# sensorboard1.net
KiCad netlist of a schematic drawn in EAGLE
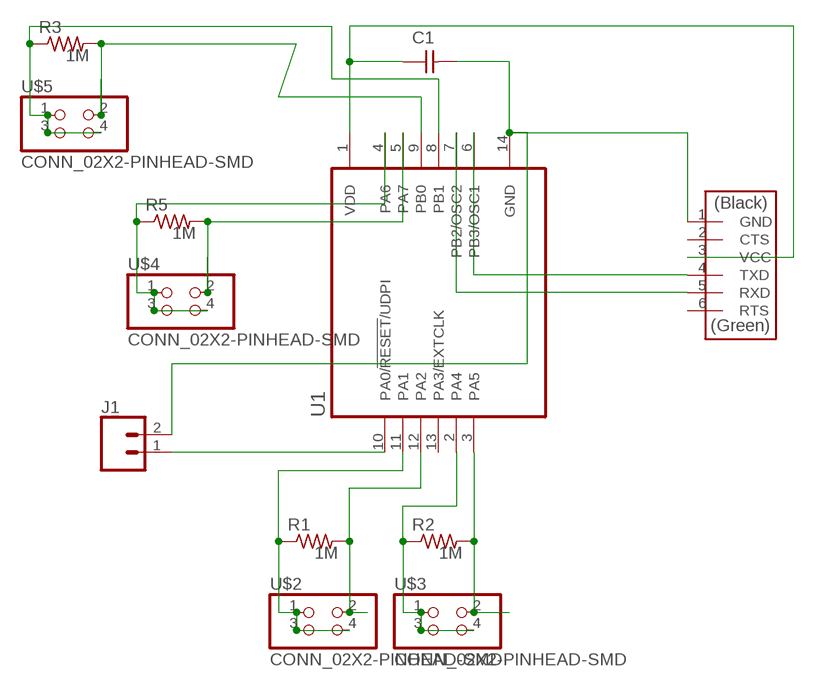
[diagram p0: schematic, sheet 1]

(export (version "E")
  (design (tool "Eeschema 10.0.6"))
  (components
    (comp (ref "C1")
      (value "CAP_UNPOLARIZEDFAB")
      (footprint "eagle-import:C1206FAB")
      (libsource (lib "eagle-import") (part "CAP_UNPOLARIZEDFAB"))
    )
    (comp (ref "J1")
      (value "CONN_02LOCK_LONGPADS")
      (footprint "eagle-import:1X02_LOCK_LONGPADS")
      (libsource (lib "eagle-import") (part "CONN_02LOCK_LONGPADS"))
    )
    (comp (ref "R1")
      (value "R1206FAB")
      (footprint "eagle-import:R1206FAB")
      (fields (field (name "R1") "1M"))
      (libsource (lib "eagle-import") (part "R1206FAB"))
    )
    (comp (ref "R2")
      (value "R1206FAB")
      (footprint "eagle-import:R1206FAB")
      (fields (field (name "R1") "1M"))
      (libsource (lib "eagle-import") (part "R1206FAB"))
    )
    (comp (ref "R3")
      (value "R1206FAB")
      (footprint "eagle-import:R1206FAB")
      (fields (field (name "R1") "1M"))
      (libsource (lib "eagle-import") (part "R1206FAB"))
    )
    (comp (ref "R5")
      (value "R1206FAB")
      (footprint "eagle-import:R1206FAB")
      (fields (field (name "R1") "1M"))
      (libsource (lib "eagle-import") (part "R1206FAB"))
    )
    (comp (ref "U$1")
      (value "CONN_06_FTDI-SMD-HEADER")
      (footprint "eagle-import:1X06SMD")
      (libsource (lib "eagle-import") (part "CONN_06_FTDI-SMD-HEADER"))
    )
    (comp (ref "U$2")
      (value "CONN_02X2-PINHEAD-SMD")
      (footprint "eagle-import:2X02SMD")
      (libsource (lib "eagle-import") (part "CONN_02X2-PINHEAD-SMD"))
    )
    (comp (ref "U$3")
      (value "CONN_02X2-PINHEAD-SMD")
      (footprint "eagle-import:2X02SMD")
      (libsource (lib "eagle-import") (part "CONN_02X2-PINHEAD-SMD"))
    )
    (comp (ref "U$4")
      (value "CONN_02X2-PINHEAD-SMD")
      (footprint "eagle-import:2X02SMD")
      (libsource (lib "eagle-import") (part "CONN_02X2-PINHEAD-SMD"))
    )
    (comp (ref "U$5")
      (value "CONN_02X2-PINHEAD-SMD")
      (footprint "eagle-import:2X02SMD")
      (libsource (lib "eagle-import") (part "CONN_02X2-PINHEAD-SMD"))
    )
    (comp (ref "U1")
      (value "ATTINY1614-SSNR")
      (footprint "eagle-import:SOIC127P600X175-14N")
      (fields (field (name "MF") "Microchip"))
      (libsource (lib "eagle-import") (part "ATTINY1614-SSNR"))
    )
  )
  (nets
    (net (code "1") (name "Net-(U$1-GND)") (class "Default")
      (node (ref "C1") (pin "2") (pinfunction "2_2") (pintype "passive"))
      (node (ref "J1") (pin "2") (pinfunction "2_2") (pintype "passive"))
      (node (ref "U$1") (pin "1") (pinfunction "GND_1") (pintype "bidirectional"))
      (node (ref "U1") (pin "14") (pinfunction "GND_14") (pintype "power_in"))
    )
    (net (code "2") (name "Net-(U$1-RXD)") (class "Default")
      (node (ref "U$1") (pin "5") (pinfunction "RXD_5") (pintype "bidirectional"))
      (node (ref "U1") (pin "7") (pinfunction "PB2/OSC2_7") (pintype "bidirectional"))
    )
    (net (code "3") (name "Net-(U$1-TXD)") (class "Default")
      (node (ref "U$1") (pin "4") (pinfunction "TXD_4") (pintype "bidirectional"))
      (node (ref "U1") (pin "6") (pinfunction "PB3/OSC1_6") (pintype "bidirectional"))
    )
    (net (code "4") (name "Net-(U$1-VCC)") (class "Default")
      (node (ref "C1") (pin "1") (pinfunction "1_1") (pintype "passive"))
      (node (ref "U$1") (pin "3") (pinfunction "VCC_3") (pintype "bidirectional"))
      (node (ref "U1") (pin "1") (pinfunction "VDD_1") (pintype "power_in"))
    )
    (net (code "5") (name "Net-(U1-PA0{slash}~{RESET}{slash}UDPI)") (class "Default")
      (node (ref "J1") (pin "1") (pinfunction "1_1") (pintype "passive"))
      (node (ref "U1") (pin "10") (pinfunction "PA0/~{RESET}/UDPI_10") (pintype "bidirectional"))
    )
    (net (code "6") (name "Net-(U1-PA1)") (class "Default")
      (node (ref "R1") (pin "1") (pinfunction "1_1") (pintype "passive"))
      (node (ref "U$2") (pin "1") (pinfunction "1_1") (pintype "passive"))
      (node (ref "U$2") (pin "3") (pinfunction "3_3") (pintype "passive"))
      (node (ref "U$2") (pin "4") (pinfunction "4_4") (pintype "passive"))
      (node (ref "U1") (pin "11") (pinfunction "PA1_11") (pintype "bidirectional"))
    )
    (net (code "7") (name "Net-(U1-PA2)") (class "Default")
      (node (ref "R1") (pin "2") (pinfunction "2_2") (pintype "passive"))
      (node (ref "U$2") (pin "2") (pinfunction "2_2") (pintype "passive"))
      (node (ref "U1") (pin "12") (pinfunction "PA2_12") (pintype "bidirectional"))
    )
    (net (code "8") (name "Net-(U1-PA4)") (class "Default")
      (node (ref "R2") (pin "1") (pinfunction "1_1") (pintype "passive"))
      (node (ref "U$3") (pin "1") (pinfunction "1_1") (pintype "passive"))
      (node (ref "U$3") (pin "3") (pinfunction "3_3") (pintype "passive"))
      (node (ref "U$3") (pin "4") (pinfunction "4_4") (pintype "passive"))
      (node (ref "U1") (pin "2") (pinfunction "PA4_2") (pintype "bidirectional"))
    )
    (net (code "9") (name "Net-(U1-PA5)") (class "Default")
      (node (ref "R2") (pin "2") (pinfunction "2_2") (pintype "passive"))
      (node (ref "U$3") (pin "2") (pinfunction "2_2") (pintype "passive"))
      (node (ref "U1") (pin "3") (pinfunction "PA5_3") (pintype "bidirectional"))
    )
    (net (code "10") (name "Net-(U1-PA6)") (class "Default")
      (node (ref "R5") (pin "1") (pinfunction "1_1") (pintype "passive"))
      (node (ref "U$4") (pin "1") (pinfunction "1_1") (pintype "passive"))
      (node (ref "U$4") (pin "3") (pinfunction "3_3") (pintype "passive"))
      (node (ref "U$4") (pin "4") (pinfunction "4_4") (pintype "passive"))
      (node (ref "U1") (pin "4") (pinfunction "PA6_4") (pintype "bidirectional"))
    )
    (net (code "11") (name "Net-(U1-PA7)") (class "Default")
      (node (ref "R5") (pin "2") (pinfunction "2_2") (pintype "passive"))
      (node (ref "U$4") (pin "2") (pinfunction "2_2") (pintype "passive"))
      (node (ref "U1") (pin "5") (pinfunction "PA7_5") (pintype "bidirectional"))
    )
    (net (code "12") (name "Net-(U1-PB0)") (class "Default")
      (node (ref "R3") (pin "2") (pinfunction "2_2") (pintype "passive"))
      (node (ref "U$5") (pin "2") (pinfunction "2_2") (pintype "passive"))
      (node (ref "U1") (pin "9") (pinfunction "PB0_9") (pintype "bidirectional"))
    )
    (net (code "13") (name "Net-(U1-PB1)") (class "Default")
      (node (ref "R3") (pin "1") (pinfunction "1_1") (pintype "passive"))
      (node (ref "U$5") (pin "1") (pinfunction "1_1") (pintype "passive"))
      (node (ref "U$5") (pin "3") (pinfunction "3_3") (pintype "passive"))
      (node (ref "U$5") (pin "4") (pinfunction "4_4") (pintype "passive"))
      (node (ref "U1") (pin "8") (pinfunction "PB1_8") (pintype "bidirectional"))
    )
    (net (code "14") (name "unconnected-(U$1-CTS-Pad2)") (class "Default")
      (node (ref "U$1") (pin "2") (pinfunction "CTS_2") (pintype "bidirectional"))
    )
    (net (code "15") (name "unconnected-(U$1-RTS-Pad6)") (class "Default")
      (node (ref "U$1") (pin "6") (pinfunction "RTS_6") (pintype "bidirectional"))
    )
    (net (code "16") (name "unconnected-(U1-PA3{slash}EXTCLK-Pad13)") (class "Default")
      (node (ref "U1") (pin "13") (pinfunction "PA3/EXTCLK_13") (pintype "bidirectional"))
    )
  )
)
